# IMU_External.net
KiCad netlist of a schematic drawn in Altium Designer
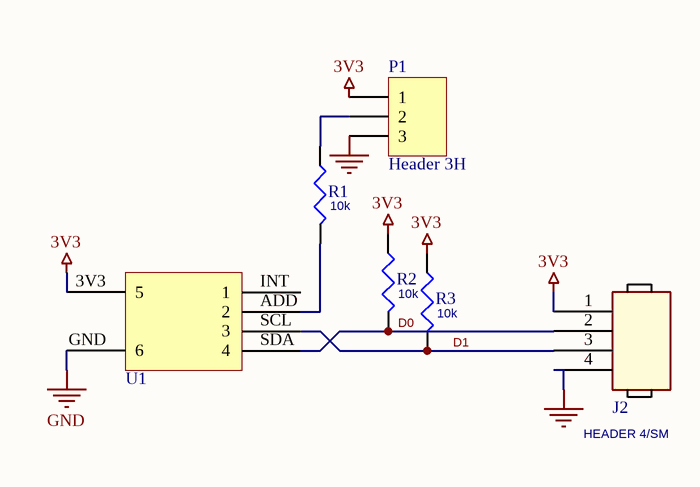
[diagram p0: IMU External.SchDoc]

(export (version "E")
  (design (tool "Eeschema 10.0.6"))
  (components
    (comp (ref "J2")
      (value "HEADER 4/SM")
      (footprint "header4")
      (libsource (lib "SLEEPTRACK2_PHASE3_Library") (part "HEADER 4/SM"))
    )
    (comp (ref "P1")
      (value "Header 3H")
      (footprint "Phase4:BNO055")
      (description "Header, 3-Pin, Right Angle")
      (fields (field (name "PUBLISHER") "Altium Limited"))
      (libsource (lib "Miscellaneous Connectors") (part "Header 3H"))
    )
    (comp (ref "R1")
      (value "10k")
      (footprint "RESC402N")
      (description "RES SMD 10K OHM 1% 1/16W 0402")
      (libsource (lib "SLEEPTRACK2_PHASE3_Library") (part "RC0402FR-0710KL"))
    )
    (comp (ref "R2")
      (value "10k")
      (footprint "RESC402N")
      (description "RES SMD 10K OHM 1% 1/16W 0402")
      (libsource (lib "SLEEPTRACK2_PHASE3_Library") (part "RC0402FR-0710KL"))
    )
    (comp (ref "R3")
      (value "10k")
      (footprint "RESC402N")
      (description "RES SMD 10K OHM 1% 1/16W 0402")
      (libsource (lib "SLEEPTRACK2_PHASE3_Library") (part "RC0402FR-0710KL"))
    )
    (comp (ref "U1")
      (value "BNO055 Nano")
      (footprint "BNO055")
      (description "PESKY PRODUCTS BNO-055 NANO BREAKOUT BOARD")
      (libsource (lib "SLEEPTRACK2_PHASE3_Library") (part "BNO055 Nano"))
    )
  )
  (nets
    (net (code "1") (name "/D0") (class "Default")
      (node (ref "J2") (pin "2") (pinfunction "2_2") (pintype "passive"))
      (node (ref "R2") (pin "2") (pinfunction "2_2") (pintype "passive"))
      (node (ref "U1") (pin "SDA") (pinfunction "4_SDA") (pintype "passive"))
    )
    (net (code "2") (name "/D1") (class "Default")
      (node (ref "J2") (pin "3") (pinfunction "3_3") (pintype "passive"))
      (node (ref "R3") (pin "2") (pinfunction "2_2") (pintype "passive"))
      (node (ref "U1") (pin "SCL") (pinfunction "3_SCL") (pintype "passive"))
    )
    (net (code "3") (name "3V3") (class "Default")
      (node (ref "J2") (pin "1") (pinfunction "1_1") (pintype "passive"))
      (node (ref "P1") (pin "1") (pinfunction "1_1") (pintype "passive"))
      (node (ref "R2") (pin "1") (pinfunction "1_1") (pintype "passive"))
      (node (ref "R3") (pin "1") (pinfunction "1_1") (pintype "passive"))
      (node (ref "U1") (pin "3V3") (pinfunction "5_3V3") (pintype "passive"))
    )
    (net (code "4") (name "GND") (class "Default")
      (node (ref "J2") (pin "4") (pinfunction "4_4") (pintype "passive"))
      (node (ref "P1") (pin "3") (pinfunction "3_3") (pintype "passive"))
      (node (ref "U1") (pin "GND") (pinfunction "6_GND") (pintype "passive"))
    )
    (net (code "5") (name "Net-(P1-Pad2)") (class "Default")
      (node (ref "P1") (pin "2") (pinfunction "2_2") (pintype "passive"))
      (node (ref "R1") (pin "1") (pinfunction "1_1") (pintype "passive"))
    )
    (net (code "6") (name "Net-(U1-2)") (class "Default")
      (node (ref "R1") (pin "2") (pinfunction "2_2") (pintype "passive"))
      (node (ref "U1") (pin "ADD") (pinfunction "2_ADD") (pintype "passive"))
    )
    (net (code "7") (name "unconnected-(U1-1-PadINT)") (class "Default")
      (node (ref "U1") (pin "INT") (pinfunction "1_INT") (pintype "passive"))
    )
  )
)
